# 12_CONSOLE.net
KiCad netlist of a schematic drawn in Altium Designer
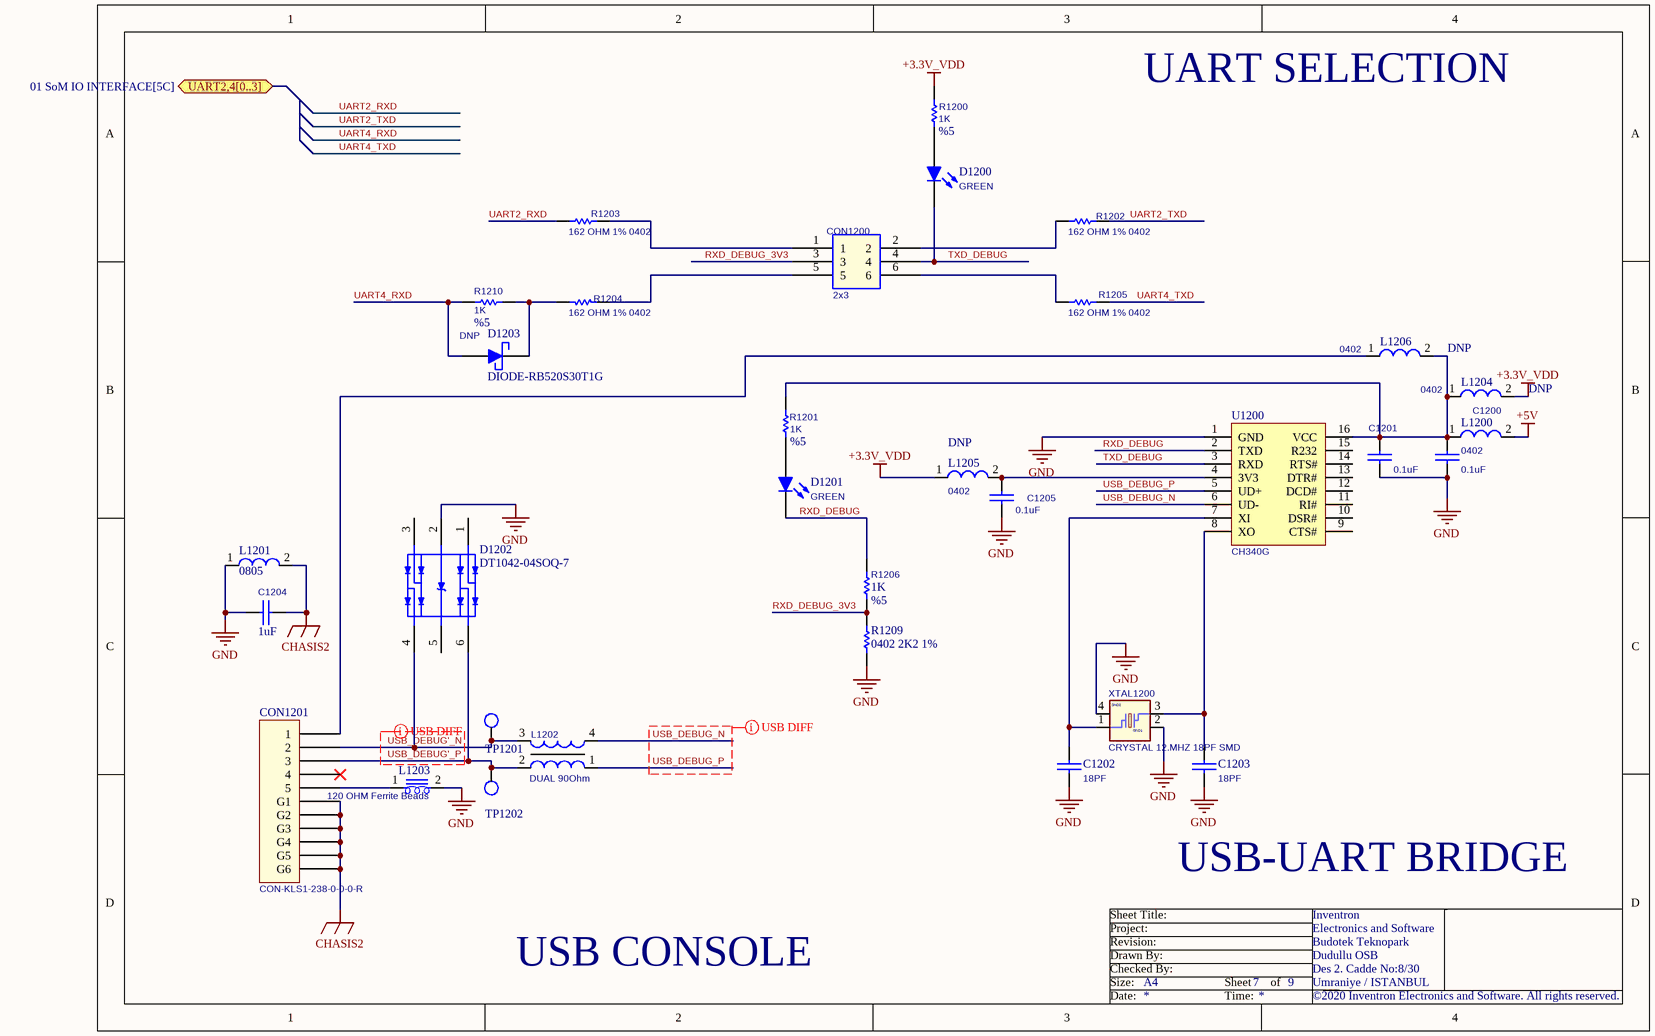
[diagram p0: 12 CONSOLE.SchDoc]

(export (version "E")
  (design (tool "Eeschema 10.0.6"))
  (components
    (comp (ref "C1200")
      (value "0.1uF")
      (footprint "0402_CC")
      (description "CAP VER 0.1UF 16V X7R 0402")
      (fields (field (name "CREATED BY") "LA") (field (name "CHECKED BY") "*"))
      (libsource (lib "ARETE_L") (part "CAP-CL05B104KO5NNNC"))
    )
    (comp (ref "C1201")
      (value "0.1uF")
      (footprint "0402_CC")
      (description "CAP VER 0.1UF 16V X7R 0402")
      (fields (field (name "CREATED BY") "LA") (field (name "CHECKED BY") "*"))
      (libsource (lib "ARETE_L") (part "CAP-CL05B104KO5NNNC"))
    )
    (comp (ref "C1202")
      (value "18PF")
      (footprint "0402_CC")
      (description "CAP CER 18PF 50V C0G/NP0 0402")
      (fields (field (name "CREATED BY") "*") (field (name "CHECKED BY") "*"))
      (libsource (lib "ARETE_SCH") (part "CAP-GCM1555C1H180JA16D"))
    )
    (comp (ref "C1203")
      (value "18PF")
      (footprint "0402_CC")
      (description "CAP CER 18PF 50V C0G/NP0 0402")
      (fields (field (name "CREATED BY") "*") (field (name "CHECKED BY") "*"))
      (libsource (lib "ARETE_SCH") (part "CAP-GCM1555C1H180JA16D"))
    )
    (comp (ref "C1204")
      (value "1uF")
      (footprint "0603_CC")
      (description "CAP CER 1UF 25V X7R 0603")
      (fields (field (name "CREATED BY") "LA") (field (name "CHECKED BY") "*"))
      (libsource (lib "ARETE_SCH") (part "CAP-CL10B105KA8NNNC"))
    )
    (comp (ref "C1205")
      (value "0.1uF")
      (footprint "0402_CC")
      (description "CAP VER 0.1UF 16V X7R 0402")
      (fields (field (name "CREATED BY") "LA") (field (name "CHECKED BY") "*"))
      (libsource (lib "ARETE_L") (part "CAP-CL05B104KO5NNNC"))
    )
    (comp (ref "CON1200")
      (value "2x3")
      (footprint "HEADER 2.54 X 3x2")
      (description "2x3 6 PIN 2.54MM HEADER")
      (fields (field (name "CREATED BY") "*") (field (name "CHECKED BY") "*"))
      (libsource (lib "ARETE_SCH") (part "CON-6 PIN 2.54MM"))
    )
    (comp (ref "CON1201")
      (value "CON-KLS1-238-0-0-0-R")
      (footprint "KLS1-238-0-0-0-R")
      (fields (field (name "CREATED BY") "OKS,EE") (field (name "CHECKED BY") "*"))
      (libsource (lib "ARETE_SCH") (part "CON-KLS1-238-0-0-0-R"))
    )
    (comp (ref "D1200")
      (value "GREEN")
      (footprint "0603_LED")
      (description "LED SMD 0603 SUPER GREEN")
      (fields (field (name "CREATED BY") "*") (field (name "CHECKED BY") "*"))
      (libsource (lib "ARETE_SCH") (part "LED-LTST-C190KRKT"))
    )
    (comp (ref "D1201")
      (value "GREEN")
      (footprint "0603_LED")
      (description "LED SMD 0603 SUPER GREEN")
      (fields (field (name "CREATED BY") "*") (field (name "CHECKED BY") "*"))
      (libsource (lib "ARETE_SCH") (part "LED-LTST-C190KRKT"))
    )
    (comp (ref "D1202")
      (value "DT1042-04SOQ-7")
      (footprint "DIODE-DT1042-04SOQ-7")
      (description "HDMI TVS DIODE")
      (fields (field (name "CREATED BY") "E.E") (field (name "CHECKED BY") "*"))
      (libsource (lib "ARETE_SCH") (part "DIODE-DT1042-04SOQ-7"))
    )
    (comp (ref "D1203")
      (value "DIODE-RB520S30T1G")
      (footprint "SOD523")
      (description "DIODE SCHOTTKY 30V 200MA SOD523")
      (fields (field (name "CREATED BY") "LA") (field (name "CHECKED BY") "*"))
      (libsource (lib "ARETE_L") (part "DIODE-RB520S30T1G"))
    )
    (comp (ref "L1200")
      (value "0402")
      (footprint "0402_RES")
      (description "0OHM 0402")
      (fields (field (name "CREATED BY") "EE") (field (name "CHECKED BY") "*"))
      (libsource (lib "ARETE_SCH") (part "IND-FERRITE (RES 0 OHM) 0402"))
    )
    (comp (ref "L1201")
      (value "0805")
      (footprint "0805")
      (description "0OHM 0805")
      (fields (field (name "CREATED BY") "EE") (field (name "CHECKED BY") "*"))
      (libsource (lib "ARETE_SCH") (part "IND-FERRITE (RES 0 OHM) 0805"))
    )
    (comp (ref "L1202")
      (value "DUAL 90Ohm")
      (footprint "DLW21H")
      (description "Common Mode Chokes Dual 90Ohm 100MHz 0.33A 0.35Ohm DCR SMD T/R")
      (fields (field (name "CREATED BY") "E.E") (field (name "CHECKED BY") "*"))
      (libsource (lib "ARETE_SCH") (part "IND-DLW21HN900SQ2L"))
    )
    (comp (ref "L1203")
      (value "120 OHM Ferrite Beads")
      (footprint "0603_RES")
      (description "Ferrite Beads Multi-Layer 120Ohm 25% 100MHz 2A 0.05Ohm DCR 0603 Automotive T/R")
      (fields (field (name "CREATED BY") "E.E") (field (name "CHECKED BY") "*"))
      (libsource (lib "ARETE_SCH") (part "IND-BLM18PG121SH1D"))
    )
    (comp (ref "L1204")
      (value "0402")
      (footprint "0402_RES")
      (description "0OHM 0402")
      (fields
        (field (name "ASSY_OPT") "DNP")
        (field (name "CREATED BY") "EE")
        (field (name "CHECKED BY") "*")
      )
      (libsource (lib "ARETE_SCH") (part "IND-FERRITE (RES 0 OHM) 0402"))
    )
    (comp (ref "L1205")
      (value "0402")
      (footprint "0402_RES")
      (description "0OHM 0402")
      (fields
        (field (name "ASSY_OPT") "DNP")
        (field (name "CREATED BY") "EE")
        (field (name "CHECKED BY") "*")
      )
      (libsource (lib "ARETE_SCH") (part "IND-FERRITE (RES 0 OHM) 0402"))
    )
    (comp (ref "L1206")
      (value "0402")
      (footprint "0402_RES")
      (description "0OHM 0402")
      (fields
        (field (name "ASSY_OPT") "DNP")
        (field (name "CREATED BY") "EE")
        (field (name "CHECKED BY") "*")
      )
      (libsource (lib "ARETE_SCH") (part "IND-FERRITE (RES 0 OHM) 0402"))
    )
    (comp (ref "R1200")
      (value "1K")
      (footprint "0402_RES")
      (description "RES 1K OHM 5% 1/16W 0402")
      (fields
        (field (name "TOLERANCE") "%5")
        (field (name "CREATED BY") "LA")
        (field (name "CHECKED BY") "*")
      )
      (libsource (lib "ARETE_SCH") (part "RES-RMCF0402JT1K00"))
    )
    (comp (ref "R1201")
      (value "1K")
      (footprint "0402_RES")
      (description "RES 1K OHM 5% 1/16W 0402")
      (fields
        (field (name "TOLERANCE") "%5")
        (field (name "CREATED BY") "LA")
        (field (name "CHECKED BY") "*")
      )
      (libsource (lib "ARETE_SCH") (part "RES-RMCF0402JT1K00"))
    )
    (comp (ref "R1202")
      (value "162 OHM 1% 0402")
      (footprint "0402_RES")
      (description "162 ±1% 0.1W, 1/10W Chip Resistor 0402 (1005 Metric) Automotive AEC-Q200 Thick Film")
      (fields (field (name "CREATED BY") "E.E") (field (name "CHECKED BY") "*"))
      (libsource (lib "ARETE_SCH") (part "RES-ERJ-2RKF1620X"))
    )
    (comp (ref "R1203")
      (value "162 OHM 1% 0402")
      (footprint "0402_RES")
      (description "162 ±1% 0.1W, 1/10W Chip Resistor 0402 (1005 Metric) Automotive AEC-Q200 Thick Film")
      (fields (field (name "CREATED BY") "E.E") (field (name "CHECKED BY") "*"))
      (libsource (lib "ARETE_SCH") (part "RES-ERJ-2RKF1620X"))
    )
    (comp (ref "R1204")
      (value "162 OHM 1% 0402")
      (footprint "0402_RES")
      (description "162 ±1% 0.1W, 1/10W Chip Resistor 0402 (1005 Metric) Automotive AEC-Q200 Thick Film")
      (fields (field (name "CREATED BY") "E.E") (field (name "CHECKED BY") "*"))
      (libsource (lib "ARETE_SCH") (part "RES-ERJ-2RKF1620X"))
    )
    (comp (ref "R1205")
      (value "162 OHM 1% 0402")
      (footprint "0402_RES")
      (description "162 ±1% 0.1W, 1/10W Chip Resistor 0402 (1005 Metric) Automotive AEC-Q200 Thick Film")
      (fields (field (name "CREATED BY") "E.E") (field (name "CHECKED BY") "*"))
      (libsource (lib "ARETE_SCH") (part "RES-ERJ-2RKF1620X"))
    )
    (comp (ref "R1206")
      (value "1K")
      (footprint "0402_RES")
      (description "RES 1K OHM 5% 1/16W 0402")
      (fields
        (field (name "TOLERANCE") "%5")
        (field (name "CREATED BY") "LA")
        (field (name "CHECKED BY") "*")
      )
      (libsource (lib "ARETE_SCH") (part "RES-RMCF0402JT1K00"))
    )
    (comp (ref "R1209")
      (value "0402 2K2 1%")
      (footprint "0402_RES")
      (fields (field (name "CREATED BY") "E.E") (field (name "CHECKED BY") "*"))
      (libsource (lib "ARETE_V2_SCH") (part "RES-CRGCQ0402F2K2"))
    )
    (comp (ref "R1210")
      (value "1K")
      (footprint "0402_RES")
      (description "RES 1K OHM 5% 1/16W 0402")
      (fields
        (field (name "ASSY_OPT") "DNP")
        (field (name "TOLERANCE") "%5")
        (field (name "CREATED BY") "LA")
        (field (name "CHECKED BY") "*")
      )
      (libsource (lib "ARETE_SCH") (part "RES-RMCF0402JT1K00"))
    )
    (comp (ref "TP1201")
      (value "TEST POINT 15")
      (footprint "testpoint_15")
      (libsource (lib "X98_CARRIER_V1R2") (part "TEST POINT 15"))
    )
    (comp (ref "TP1202")
      (value "TEST POINT 15")
      (footprint "testpoint_15")
      (libsource (lib "X98_CARRIER_V1R2") (part "TEST POINT 15"))
    )
    (comp (ref "U1200")
      (value "CH340G")
      (footprint "CH340G")
      (description "IC-340 USB INTERFACE SO16")
      (fields (field (name "CREATED BY") "E.E.") (field (name "CHECKED BY") "*"))
      (libsource (lib "ARETE_SCH") (part "IC-CH340G"))
    )
    (comp (ref "XTAL1200")
      (value "CRYSTAL 12.MHZ 18PF SMD")
      (footprint "XTLOSC4_3P2X2P5MM_SM")
      (description "CRYSTAL 12.0000MHZ 18PF SMD")
      (fields (field (name "CREATED BY") "E.E") (field (name "CHECKED BY") "*"))
      (libsource (lib "ARETE_SCH") (part "XTAL-FA-238V 12.0000MB50X-C0"))
    )
  )
  (nets
    (net (code "5") (name "+3.3V_VDD") (class "Default")
      (node (ref "L1204") (pin "2") (pinfunction "2_2") (pintype "passive"))
      (node (ref "L1205") (pin "1") (pinfunction "1_1") (pintype "passive"))
      (node (ref "R1200") (pin "1") (pinfunction "1_1") (pintype "passive"))
    )
    (net (code "6") (name "+5V") (class "Default")
      (node (ref "L1200") (pin "2") (pinfunction "2_2") (pintype "passive"))
    )
    (net (code "7") (name "/RXD_DEBUG") (class "Default")
      (node (ref "D1201") (pin "2") (pinfunction "K_2") (pintype "passive"))
      (node (ref "R1206") (pin "2") (pinfunction "2_2") (pintype "passive"))
      (node (ref "U1200") (pin "2") (pinfunction "TXD_2") (pintype "passive"))
    )
    (net (code "8") (name "/RXD_DEBUG_3V3") (class "Default")
      (node (ref "CON1200") (pin "3") (pinfunction "3_3") (pintype "passive"))
      (node (ref "R1206") (pin "1") (pinfunction "1_1") (pintype "passive"))
      (node (ref "R1209") (pin "2") (pinfunction "2_2") (pintype "passive"))
    )
    (net (code "9") (name "/TXD_DEBUG") (class "Default")
      (node (ref "CON1200") (pin "4") (pinfunction "4_4") (pintype "passive"))
      (node (ref "D1200") (pin "2") (pinfunction "K_2") (pintype "passive"))
      (node (ref "U1200") (pin "3") (pinfunction "RXD_3") (pintype "passive"))
    )
    (net (code "11") (name "/UART2_RXD") (class "Default")
      (node (ref "R1203") (pin "1") (pinfunction "1_1") (pintype "passive"))
    )
    (net (code "12") (name "/UART2_TXD") (class "Default")
      (node (ref "R1202") (pin "2") (pinfunction "2_2") (pintype "passive"))
    )
    (net (code "13") (name "/UART4_RXD") (class "Default")
      (node (ref "D1203") (pin "1") (pinfunction "A_1") (pintype "passive"))
      (node (ref "R1210") (pin "1") (pinfunction "1_1") (pintype "passive"))
    )
    (net (code "14") (name "/UART4_TXD") (class "Default")
      (node (ref "R1205") (pin "2") (pinfunction "2_2") (pintype "passive"))
    )
    (net (code "15") (name "/USB_DEBUG'_N") (class "Default")
      (node (ref "CON1201") (pin "2") (pinfunction "2_2") (pintype "passive"))
      (node (ref "D1202") (pin "4") (pinfunction "IO3_4") (pintype "passive"))
      (node (ref "L1202") (pin "3") (pinfunction "3_3") (pintype "passive"))
      (node (ref "TP1201") (pin "1") (pinfunction "1_1") (pintype "passive"))
    )
    (net (code "16") (name "/USB_DEBUG'_P") (class "Default")
      (node (ref "CON1201") (pin "3") (pinfunction "3_3") (pintype "passive"))
      (node (ref "D1202") (pin "6") (pinfunction "IO4_6") (pintype "passive"))
      (node (ref "L1202") (pin "2") (pinfunction "2_2") (pintype "passive"))
      (node (ref "TP1202") (pin "1") (pinfunction "1_1") (pintype "passive"))
    )
    (net (code "17") (name "/USB_DEBUG_N") (class "Default")
      (node (ref "L1202") (pin "4") (pinfunction "4_4") (pintype "passive"))
      (node (ref "U1200") (pin "6") (pinfunction "UD-_6") (pintype "passive"))
    )
    (net (code "18") (name "/USB_DEBUG_P") (class "Default")
      (node (ref "L1202") (pin "1") (pinfunction "1_1") (pintype "passive"))
      (node (ref "U1200") (pin "5") (pinfunction "UD+_5") (pintype "passive"))
    )
    (net (code "19") (name "CHASIS2") (class "Default")
      (node (ref "C1204") (pin "1") (pinfunction "1_1") (pintype "passive"))
      (node (ref "CON1201") (pin "G1") (pinfunction "G1_G1") (pintype "passive"))
      (node (ref "CON1201") (pin "G2") (pinfunction "G2_G2") (pintype "passive"))
      (node (ref "CON1201") (pin "G3") (pinfunction "G3_G3") (pintype "passive"))
      (node (ref "CON1201") (pin "G4") (pinfunction "G4_G4") (pintype "passive"))
      (node (ref "CON1201") (pin "G5") (pinfunction "G5_G5") (pintype "passive"))
      (node (ref "CON1201") (pin "G6") (pinfunction "G6_G6") (pintype "passive"))
      (node (ref "L1201") (pin "2") (pinfunction "2_2") (pintype "passive"))
    )
    (net (code "20") (name "GND") (class "Default")
      (node (ref "C1200") (pin "2") (pinfunction "2_2") (pintype "passive"))
      (node (ref "C1201") (pin "2") (pinfunction "2_2") (pintype "passive"))
      (node (ref "C1202") (pin "2") (pinfunction "2_2") (pintype "passive"))
      (node (ref "C1203") (pin "2") (pinfunction "2_2") (pintype "passive"))
      (node (ref "C1204") (pin "2") (pinfunction "2_2") (pintype "passive"))
      (node (ref "C1205") (pin "2") (pinfunction "2_2") (pintype "passive"))
      (node (ref "D1202") (pin "2") (pinfunction "VSS_2") (pintype "power_in"))
      (node (ref "L1201") (pin "1") (pinfunction "1_1") (pintype "passive"))
      (node (ref "L1203") (pin "2") (pinfunction "2_2") (pintype "passive"))
      (node (ref "R1209") (pin "1") (pinfunction "1_1") (pintype "passive"))
      (node (ref "U1200") (pin "1") (pinfunction "GND_1") (pintype "passive"))
      (node (ref "XTAL1200") (pin "2") (pinfunction "GND1_2") (pintype "power_in"))
      (node (ref "XTAL1200") (pin "4") (pinfunction "GND2_4") (pintype "power_in"))
    )
    (net (code "21") (name "Net-(CON1200-Pad1)") (class "Default")
      (node (ref "CON1200") (pin "1") (pinfunction "1_1") (pintype "passive"))
      (node (ref "R1203") (pin "2") (pinfunction "2_2") (pintype "passive"))
    )
    (net (code "22") (name "Net-(CON1200-Pad2)") (class "Default")
      (node (ref "CON1200") (pin "2") (pinfunction "2_2") (pintype "passive"))
      (node (ref "R1202") (pin "1") (pinfunction "1_1") (pintype "passive"))
    )
    (net (code "23") (name "Net-(CON1200-Pad5)") (class "Default")
      (node (ref "CON1200") (pin "5") (pinfunction "5_5") (pintype "passive"))
      (node (ref "R1204") (pin "2") (pinfunction "2_2") (pintype "passive"))
    )
    (net (code "24") (name "Net-(CON1200-Pad6)") (class "Default")
      (node (ref "CON1200") (pin "6") (pinfunction "6_6") (pintype "passive"))
      (node (ref "R1205") (pin "1") (pinfunction "1_1") (pintype "passive"))
    )
    (net (code "25") (name "Net-(CON1201-Pad1)") (class "Default")
      (node (ref "CON1201") (pin "1") (pinfunction "1_1") (pintype "passive"))
      (node (ref "L1206") (pin "1") (pinfunction "1_1") (pintype "passive"))
    )
    (net (code "26") (name "Net-(CON1201-Pad5)") (class "Default")
      (node (ref "CON1201") (pin "5") (pinfunction "5_5") (pintype "passive"))
      (node (ref "L1203") (pin "1") (pinfunction "1_1") (pintype "passive"))
    )
    (net (code "27") (name "Net-(D1200-A)") (class "Default")
      (node (ref "D1200") (pin "1") (pinfunction "A_1") (pintype "passive"))
      (node (ref "R1200") (pin "2") (pinfunction "2_2") (pintype "passive"))
    )
    (net (code "28") (name "Net-(D1201-A)") (class "Default")
      (node (ref "D1201") (pin "1") (pinfunction "A_1") (pintype "passive"))
      (node (ref "R1201") (pin "2") (pinfunction "2_2") (pintype "passive"))
    )
    (net (code "29") (name "Net-(D1203-K)") (class "Default")
      (node (ref "D1203") (pin "2") (pinfunction "K_2") (pintype "passive"))
      (node (ref "R1204") (pin "1") (pinfunction "1_1") (pintype "passive"))
      (node (ref "R1210") (pin "2") (pinfunction "2_2") (pintype "passive"))
    )
    (net (code "30") (name "Net-(U1200-3V3)") (class "Default")
      (node (ref "C1205") (pin "1") (pinfunction "1_1") (pintype "passive"))
      (node (ref "L1205") (pin "2") (pinfunction "2_2") (pintype "passive"))
      (node (ref "U1200") (pin "4") (pinfunction "3V3_4") (pintype "passive"))
    )
    (net (code "31") (name "Net-(U1200-VCC)") (class "Default")
      (node (ref "C1200") (pin "1") (pinfunction "1_1") (pintype "passive"))
      (node (ref "C1201") (pin "1") (pinfunction "1_1") (pintype "passive"))
      (node (ref "L1200") (pin "1") (pinfunction "1_1") (pintype "passive"))
      (node (ref "L1204") (pin "1") (pinfunction "1_1") (pintype "passive"))
      (node (ref "L1206") (pin "2") (pinfunction "2_2") (pintype "passive"))
      (node (ref "R1201") (pin "1") (pinfunction "1_1") (pintype "passive"))
      (node (ref "U1200") (pin "16") (pinfunction "VCC_16") (pintype "passive"))
    )
    (net (code "32") (name "Net-(U1200-XI)") (class "Default")
      (node (ref "C1202") (pin "1") (pinfunction "1_1") (pintype "passive"))
      (node (ref "U1200") (pin "7") (pinfunction "XI_7") (pintype "passive"))
      (node (ref "XTAL1200") (pin "1") (pinfunction "1_1") (pintype "passive"))
    )
    (net (code "33") (name "Net-(U1200-XO)") (class "Default")
      (node (ref "C1203") (pin "1") (pinfunction "1_1") (pintype "passive"))
      (node (ref "U1200") (pin "8") (pinfunction "XO_8") (pintype "passive"))
      (node (ref "XTAL1200") (pin "3") (pinfunction "3_3") (pintype "passive"))
    )
    (net (code "34") (name "unconnected-(CON1201-Pad4)") (class "Default")
      (node (ref "CON1201") (pin "4") (pinfunction "4_4") (pintype "passive+no_connect"))
    )
    (net (code "35") (name "unconnected-(D1202-IO1-Pad1)") (class "Default")
      (node (ref "D1202") (pin "1") (pinfunction "IO1_1") (pintype "passive"))
    )
    (net (code "36") (name "unconnected-(D1202-IO2-Pad3)") (class "Default")
      (node (ref "D1202") (pin "3") (pinfunction "IO2_3") (pintype "passive"))
    )
    (net (code "37") (name "unconnected-(D1202-VCC-Pad5)") (class "Default")
      (node (ref "D1202") (pin "5") (pinfunction "VCC_5") (pintype "power_in"))
    )
    (net (code "38") (name "unconnected-(U1200-CTS#-Pad9)") (class "Default")
      (node (ref "U1200") (pin "9") (pinfunction "CTS#_9") (pintype "passive"))
    )
    (net (code "39") (name "unconnected-(U1200-DCD#-Pad12)") (class "Default")
      (node (ref "U1200") (pin "12") (pinfunction "DCD#_12") (pintype "passive"))
    )
    (net (code "40") (name "unconnected-(U1200-DSR#-Pad10)") (class "Default")
      (node (ref "U1200") (pin "10") (pinfunction "DSR#_10") (pintype "passive"))
    )
    (net (code "41") (name "unconnected-(U1200-DTR#-Pad13)") (class "Default")
      (node (ref "U1200") (pin "13") (pinfunction "DTR#_13") (pintype "passive"))
    )
    (net (code "42") (name "unconnected-(U1200-R232-Pad15)") (class "Default")
      (node (ref "U1200") (pin "15") (pinfunction "R232_15") (pintype "passive"))
    )
    (net (code "43") (name "unconnected-(U1200-RI#-Pad11)") (class "Default")
      (node (ref "U1200") (pin "11") (pinfunction "RI#_11") (pintype "passive"))
    )
    (net (code "44") (name "unconnected-(U1200-RTS#-Pad14)") (class "Default")
      (node (ref "U1200") (pin "14") (pinfunction "RTS#_14") (pintype "passive"))
    )
  )
)
